# 3-Display.net
KiCad netlist of a schematic drawn in Altium Designer
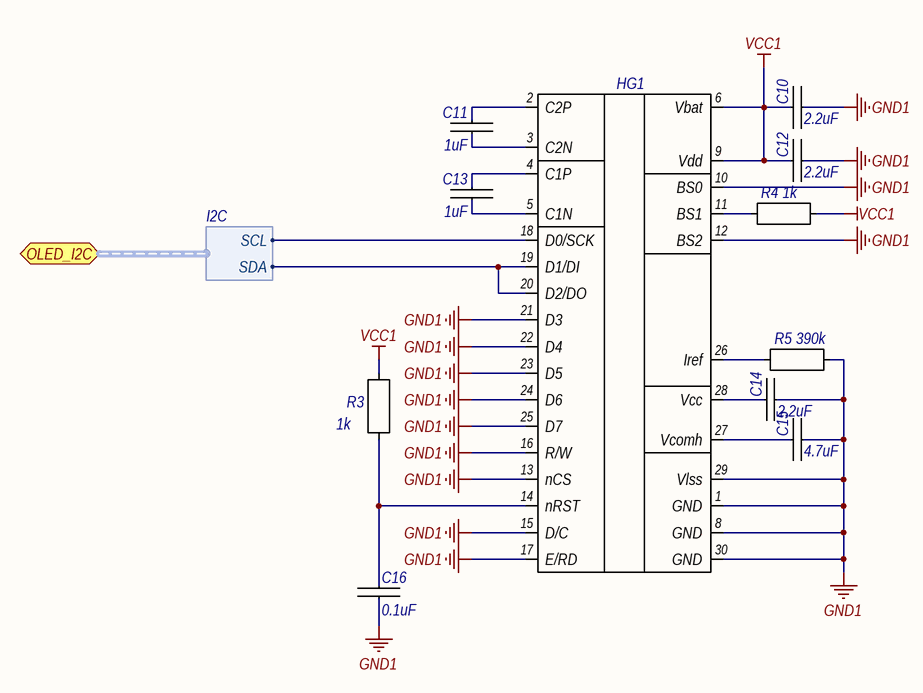
[diagram p0: 3-Display.SchDoc]

(export (version "E")
  (design (tool "Eeschema 10.0.6"))
  (components
    (comp (ref "C10")
      (value "2.2uF")
      (footprint "CHIP_0402_C")
      (description "Конденсатор")
      (fields (field (name "PARTNUMBER") "GRM155R61A225KE95D") (field (name "MFG") "MURATA"))
      (libsource (lib "RCL") (part "Конденсатор"))
    )
    (comp (ref "C11")
      (value "1uF")
      (footprint "CHIP_0402_C")
      (description "Конденсатор")
      (fields (field (name "PARTNUMBER") "CC0402KRX5R5BB105") (field (name "MFG") "YAGEO"))
      (libsource (lib "RCL") (part "Конденсатор"))
    )
    (comp (ref "C12")
      (value "2.2uF")
      (footprint "CHIP_0402_C")
      (description "Конденсатор")
      (fields (field (name "PARTNUMBER") "GRM155R61A225KE95D") (field (name "MFG") "MURATA"))
      (libsource (lib "RCL") (part "Конденсатор"))
    )
    (comp (ref "C13")
      (value "1uF")
      (footprint "CHIP_0402_C")
      (description "Конденсатор")
      (fields (field (name "PARTNUMBER") "CC0402KRX5R5BB105") (field (name "MFG") "YAGEO"))
      (libsource (lib "RCL") (part "Конденсатор"))
    )
    (comp (ref "C14")
      (value "2.2uF")
      (footprint "CHIP_0402_C")
      (description "Конденсатор")
      (fields (field (name "PARTNUMBER") "GRM155R61A225KE95D") (field (name "MFG") "MURATA"))
      (libsource (lib "RCL") (part "Конденсатор"))
    )
    (comp (ref "C15")
      (value "4.7uF")
      (footprint "CHIP_0402_C")
      (description "Конденсатор")
      (fields (field (name "PARTNUMBER") "GRM155R60J475ME87D") (field (name "MFG") "MURATA"))
      (libsource (lib "RCL") (part "Конденсатор"))
    )
    (comp (ref "C16")
      (value "0.1uF")
      (footprint "CHIP_0402_C")
      (description "Конденсатор")
      (fields (field (name "PARTNUMBER") "CC0402KRX7R7BB104") (field (name "MFG") "YAGEO"))
      (libsource (lib "RCL") (part "Конденсатор"))
    )
    (comp (ref "HG1")
      (value "OLED 0,96")
      (footprint "OLED 0.96")
      (description "OLED, Serial, 0.96\"")
      (fields (field (name "PARTNUMBER") "SSD1306 OLED Module"))
      (libsource (lib "modules") (part "OLED 0,96"))
    )
    (comp (ref "R3")
      (value "1k")
      (footprint "CHIP_0402_R")
      (description "Резистор")
      (fields (field (name "PARTNUMBER") "RC0402FR-071KL") (field (name "MFG") "YAGEO"))
      (libsource (lib "RCL") (part "Резистор"))
    )
    (comp (ref "R4")
      (value "1k")
      (footprint "CHIP_0402_R")
      (description "Резистор")
      (fields (field (name "PARTNUMBER") "RC0402FR-071KL") (field (name "MFG") "YAGEO"))
      (libsource (lib "RCL") (part "Резистор"))
    )
    (comp (ref "R5")
      (value "390k")
      (footprint "CHIP_0402_R")
      (description "Резистор")
      (fields (field (name "PARTNUMBER") "RC0402FR-07390KL") (field (name "MFG") "YAGEO"))
      (libsource (lib "RCL") (part "Резистор"))
    )
  )
  (nets
    (net (code "2") (name "/SCL") (class "Default")
      (node (ref "HG1") (pin "18") (pinfunction "D0/SCK_18") (pintype "passive"))
    )
    (net (code "3") (name "/SDA") (class "Default")
      (node (ref "HG1") (pin "19") (pinfunction "D1/DI_19") (pintype "passive"))
      (node (ref "HG1") (pin "20") (pinfunction "D2/DO_20") (pintype "passive"))
    )
    (net (code "5") (name "GND1") (class "Default")
      (node (ref "C10") (pin "1") (pinfunction "1_1") (pintype "passive"))
      (node (ref "C12") (pin "1") (pinfunction "1_1") (pintype "passive"))
      (node (ref "C14") (pin "1") (pinfunction "1_1") (pintype "passive"))
      (node (ref "C15") (pin "1") (pinfunction "1_1") (pintype "passive"))
      (node (ref "C16") (pin "1") (pinfunction "1_1") (pintype "passive"))
      (node (ref "HG1") (pin "1") (pinfunction "GND_1") (pintype "passive"))
      (node (ref "HG1") (pin "10") (pinfunction "BS0_10") (pintype "passive"))
      (node (ref "HG1") (pin "12") (pinfunction "BS2_12") (pintype "passive"))
      (node (ref "HG1") (pin "13") (pinfunction "nCS_13") (pintype "passive"))
      (node (ref "HG1") (pin "15") (pinfunction "D/C_15") (pintype "passive"))
      (node (ref "HG1") (pin "16") (pinfunction "R/W_16") (pintype "passive"))
      (node (ref "HG1") (pin "17") (pinfunction "E/RD_17") (pintype "passive"))
      (node (ref "HG1") (pin "21") (pinfunction "D3_21") (pintype "passive"))
      (node (ref "HG1") (pin "22") (pinfunction "D4_22") (pintype "passive"))
      (node (ref "HG1") (pin "23") (pinfunction "D5_23") (pintype "passive"))
      (node (ref "HG1") (pin "24") (pinfunction "D6_24") (pintype "passive"))
      (node (ref "HG1") (pin "25") (pinfunction "D7_25") (pintype "passive"))
      (node (ref "HG1") (pin "29") (pinfunction "Vlss_29") (pintype "passive"))
      (node (ref "HG1") (pin "30") (pinfunction "GND_30") (pintype "passive"))
      (node (ref "HG1") (pin "8") (pinfunction "GND_8") (pintype "passive"))
      (node (ref "R5") (pin "2") (pinfunction "2_2") (pintype "passive"))
    )
    (net (code "6") (name "Net-(HG1-BS1)") (class "Default")
      (node (ref "HG1") (pin "11") (pinfunction "BS1_11") (pintype "passive"))
      (node (ref "R4") (pin "1") (pinfunction "1_1") (pintype "passive"))
    )
    (net (code "7") (name "Net-(HG1-C1N)") (class "Default")
      (node (ref "C13") (pin "1") (pinfunction "1_1") (pintype "passive"))
      (node (ref "HG1") (pin "5") (pinfunction "C1N_5") (pintype "passive"))
    )
    (net (code "8") (name "Net-(HG1-C1P)") (class "Default")
      (node (ref "C13") (pin "2") (pinfunction "2_2") (pintype "passive"))
      (node (ref "HG1") (pin "4") (pinfunction "C1P_4") (pintype "passive"))
    )
    (net (code "9") (name "Net-(HG1-C2N)") (class "Default")
      (node (ref "C11") (pin "1") (pinfunction "1_1") (pintype "passive"))
      (node (ref "HG1") (pin "3") (pinfunction "C2N_3") (pintype "passive"))
    )
    (net (code "10") (name "Net-(HG1-C2P)") (class "Default")
      (node (ref "C11") (pin "2") (pinfunction "2_2") (pintype "passive"))
      (node (ref "HG1") (pin "2") (pinfunction "C2P_2") (pintype "passive"))
    )
    (net (code "11") (name "Net-(HG1-Iref)") (class "Default")
      (node (ref "HG1") (pin "26") (pinfunction "Iref_26") (pintype "passive"))
      (node (ref "R5") (pin "1") (pinfunction "1_1") (pintype "passive"))
    )
    (net (code "12") (name "Net-(HG1-Vcc)") (class "Default")
      (node (ref "C14") (pin "2") (pinfunction "2_2") (pintype "passive"))
      (node (ref "HG1") (pin "28") (pinfunction "Vcc_28") (pintype "passive"))
    )
    (net (code "13") (name "Net-(HG1-Vcomh)") (class "Default")
      (node (ref "C15") (pin "2") (pinfunction "2_2") (pintype "passive"))
      (node (ref "HG1") (pin "27") (pinfunction "Vcomh_27") (pintype "passive"))
    )
    (net (code "14") (name "Net-(HG1-nRST)") (class "Default")
      (node (ref "C16") (pin "2") (pinfunction "2_2") (pintype "passive"))
      (node (ref "HG1") (pin "14") (pinfunction "nRST_14") (pintype "passive"))
      (node (ref "R3") (pin "1") (pinfunction "1_1") (pintype "passive"))
    )
    (net (code "15") (name "VCC1") (class "Default")
      (node (ref "C10") (pin "2") (pinfunction "2_2") (pintype "passive"))
      (node (ref "C12") (pin "2") (pinfunction "2_2") (pintype "passive"))
      (node (ref "HG1") (pin "6") (pinfunction "Vbat_6") (pintype "passive"))
      (node (ref "HG1") (pin "9") (pinfunction "Vdd_9") (pintype "passive"))
      (node (ref "R3") (pin "2") (pinfunction "2_2") (pintype "passive"))
      (node (ref "R4") (pin "2") (pinfunction "2_2") (pintype "passive"))
    )
  )
)
